# ME433.net
KiCad netlist of a schematic drawn in EAGLE
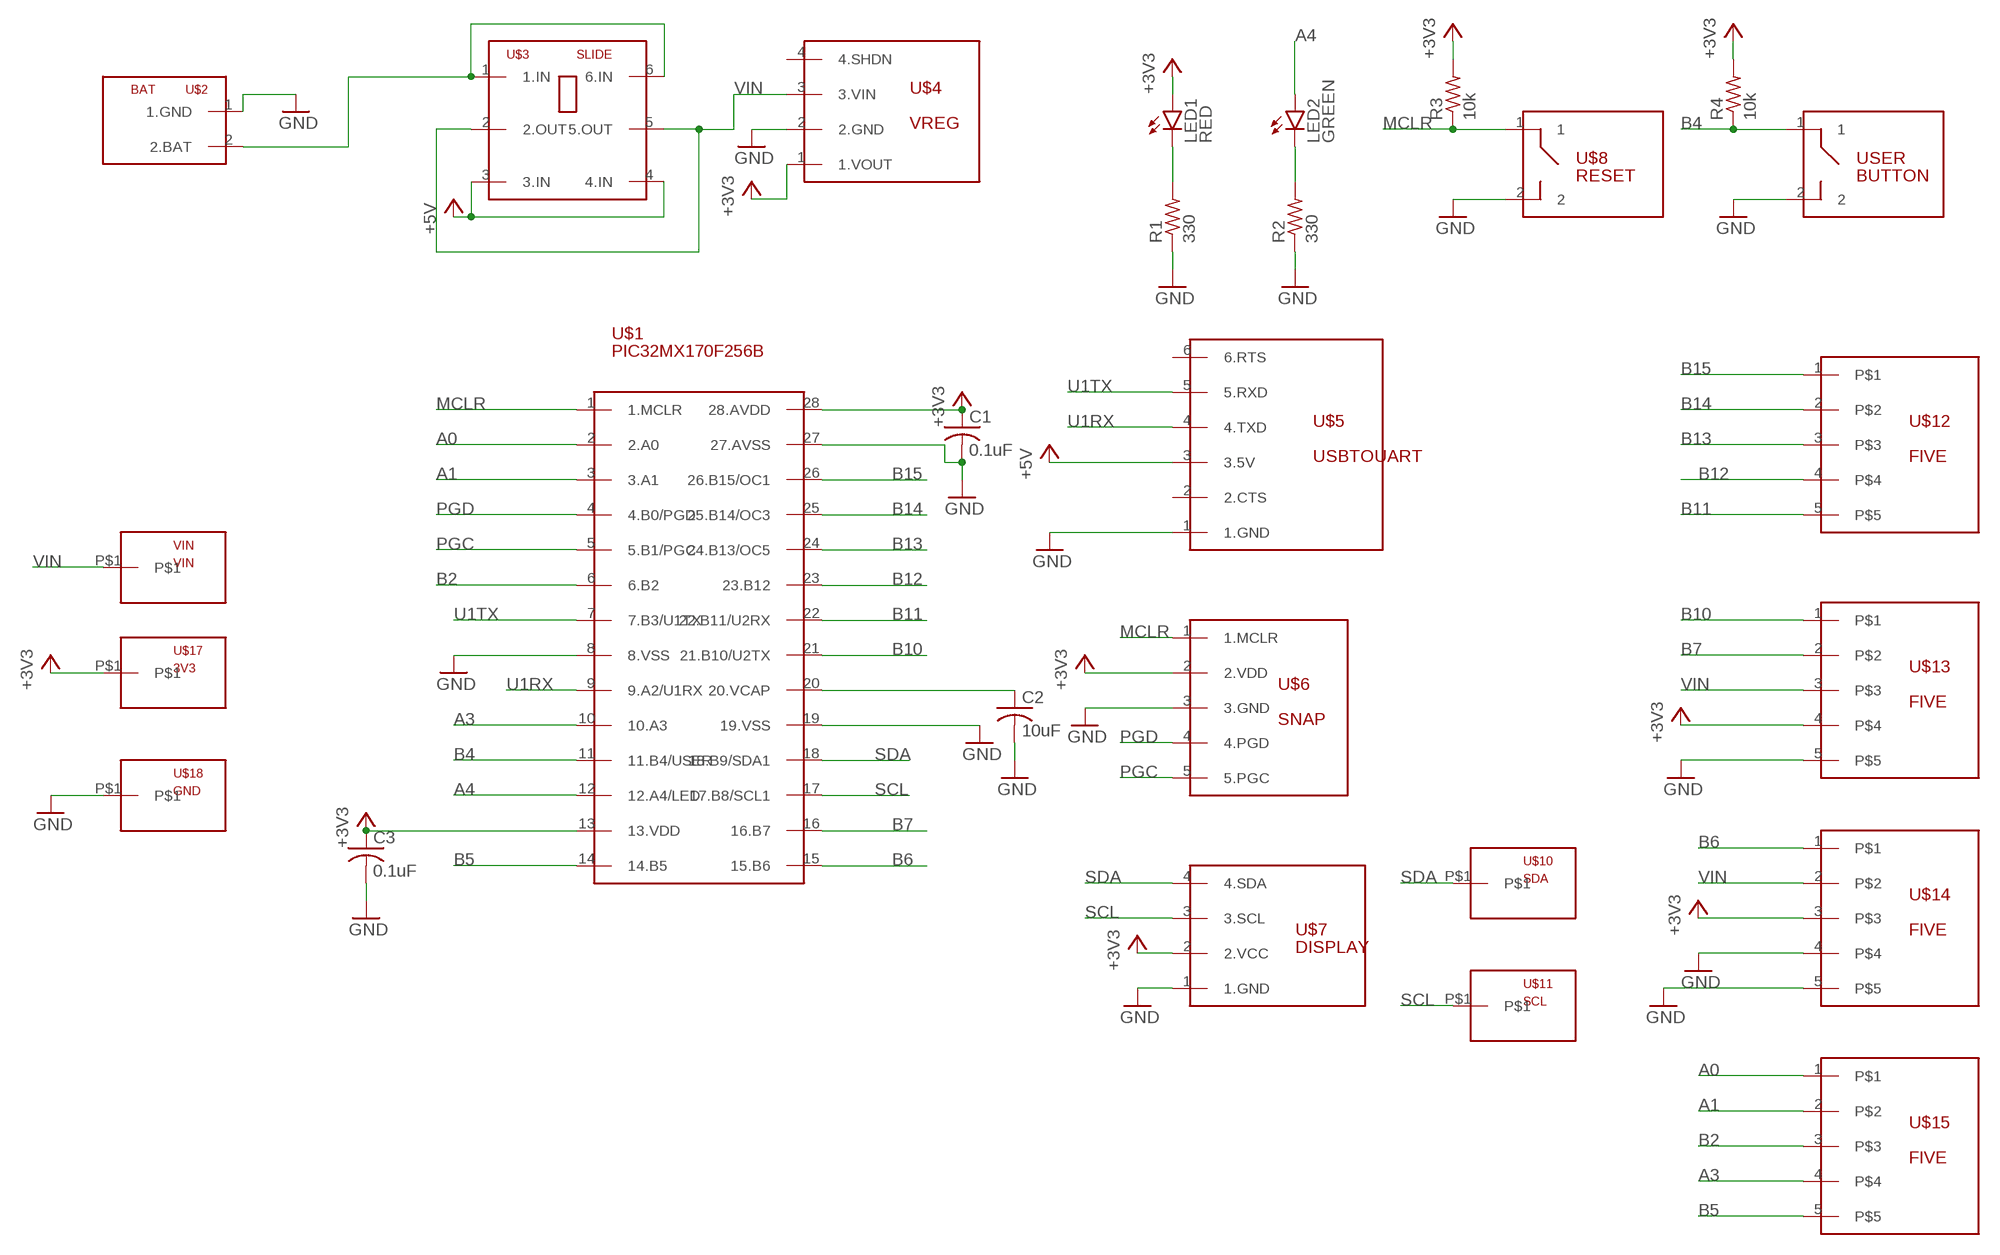
[diagram p0: schematic, sheet 1]

(export (version "E")
  (design (tool "Eeschema 10.0.6"))
  (components
    (comp (ref "C1")
      (value "0.1uF")
      (footprint "eagle-import:C025-024X044")
      (libsource (lib "eagle-import") (part "C-US025-024X044"))
    )
    (comp (ref "C2")
      (value "10uF")
      (footprint "eagle-import:C025-024X044")
      (libsource (lib "eagle-import") (part "C-US025-024X044"))
    )
    (comp (ref "C3")
      (value "0.1uF")
      (footprint "eagle-import:C025-024X044")
      (libsource (lib "eagle-import") (part "C-US025-024X044"))
    )
    (comp (ref "LED1")
      (value "RED")
      (footprint "eagle-import:LED3MM")
      (libsource (lib "eagle-import") (part "LED3MM"))
    )
    (comp (ref "LED2")
      (value "GREEN")
      (footprint "eagle-import:LED3MM")
      (libsource (lib "eagle-import") (part "LED3MM"))
    )
    (comp (ref "R1")
      (value "330")
      (footprint "eagle-import:0207_7")
      (libsource (lib "eagle-import") (part "R-US_0207/7"))
    )
    (comp (ref "R2")
      (value "330")
      (footprint "eagle-import:0207_7")
      (libsource (lib "eagle-import") (part "R-US_0207/7"))
    )
    (comp (ref "R3")
      (value "10k")
      (footprint "eagle-import:0207_7")
      (libsource (lib "eagle-import") (part "R-US_0207/7"))
    )
    (comp (ref "R4")
      (value "10k")
      (footprint "eagle-import:0207_7")
      (libsource (lib "eagle-import") (part "R-US_0207/7"))
    )
    (comp (ref "U$1")
      (value "PIC32MX170F256B")
      (footprint "eagle-import:DIL28-3")
      (libsource (lib "eagle-import") (part "PIC32MX170F256B"))
    )
    (comp (ref "U$2")
      (value "BAT")
      (footprint "eagle-import:BAT")
      (libsource (lib "eagle-import") (part "BAT"))
    )
    (comp (ref "U$3")
      (value "SLIDE")
      (footprint "eagle-import:SLIDE")
      (libsource (lib "eagle-import") (part "SLIDE"))
    )
    (comp (ref "U$4")
      (value "VREG")
      (footprint "eagle-import:VREG")
      (libsource (lib "eagle-import") (part "VREG"))
    )
    (comp (ref "U$5")
      (value "USBTOUART")
      (footprint "eagle-import:USBTOUART")
      (libsource (lib "eagle-import") (part "USBTOUART"))
    )
    (comp (ref "U$6")
      (value "SNAP")
      (footprint "eagle-import:SNAP")
      (libsource (lib "eagle-import") (part "SNAP"))
    )
    (comp (ref "U$7")
      (value "DISPLAY")
      (footprint "eagle-import:DISPLAY")
      (libsource (lib "eagle-import") (part "DISPLAY"))
    )
    (comp (ref "U$8")
      (value "RESET")
      (footprint "eagle-import:BUTTON")
      (libsource (lib "eagle-import") (part "BUTTON"))
    )
    (comp (ref "U$10") (value "SDA") (footprint "eagle-import:1") (libsource (lib "eagle-import") (part "1")))
    (comp (ref "U$11") (value "SCL") (footprint "eagle-import:1") (libsource (lib "eagle-import") (part "1")))
    (comp (ref "U$12")
      (value "FIVE")
      (footprint "eagle-import:FIVE")
      (libsource (lib "eagle-import") (part "FIVE"))
    )
    (comp (ref "U$13")
      (value "FIVE")
      (footprint "eagle-import:FIVE")
      (libsource (lib "eagle-import") (part "FIVE"))
    )
    (comp (ref "U$14")
      (value "FIVE")
      (footprint "eagle-import:FIVE")
      (libsource (lib "eagle-import") (part "FIVE"))
    )
    (comp (ref "U$15")
      (value "FIVE")
      (footprint "eagle-import:FIVE")
      (libsource (lib "eagle-import") (part "FIVE"))
    )
    (comp (ref "U$17") (value "3V3") (footprint "eagle-import:1") (libsource (lib "eagle-import") (part "1")))
    (comp (ref "U$18") (value "GND") (footprint "eagle-import:1") (libsource (lib "eagle-import") (part "1")))
    (comp (ref "USER")
      (value "BUTTON")
      (footprint "eagle-import:BUTTON")
      (libsource (lib "eagle-import") (part "BUTTON"))
    )
    (comp (ref "VIN") (value "VIN") (footprint "eagle-import:1") (libsource (lib "eagle-import") (part "1")))
  )
  (nets
    (net (code "1") (name "+3V3") (class "Default")
      (node (ref "C1") (pin "1") (pinfunction "1_1") (pintype "passive"))
      (node (ref "C3") (pin "1") (pinfunction "1_1") (pintype "passive"))
      (node (ref "LED1") (pin "A") (pinfunction "A_A") (pintype "passive"))
      (node (ref "R3") (pin "2") (pinfunction "2_2") (pintype "passive"))
      (node (ref "R4") (pin "2") (pinfunction "2_2") (pintype "passive"))
      (node (ref "U$1") (pin "13") (pinfunction "13.VDD_13") (pintype "bidirectional"))
      (node (ref "U$1") (pin "28") (pinfunction "28.AVDD_28") (pintype "bidirectional"))
      (node (ref "U$13") (pin "4") (pinfunction "P$4_4") (pintype "bidirectional"))
      (node (ref "U$14") (pin "3") (pinfunction "P$3_3") (pintype "bidirectional"))
      (node (ref "U$17") (pin "P$1") (pinfunction "P$1_P$1") (pintype "bidirectional"))
      (node (ref "U$4") (pin "1") (pinfunction "1.VOUT_1") (pintype "bidirectional"))
      (node (ref "U$6") (pin "2") (pinfunction "2.VDD_2") (pintype "bidirectional"))
      (node (ref "U$7") (pin "2") (pinfunction "2.VCC_2") (pintype "bidirectional"))
    )
    (net (code "2") (name "+5V") (class "Default")
      (node (ref "U$3") (pin "3") (pinfunction "3.IN_3") (pintype "bidirectional"))
      (node (ref "U$3") (pin "4") (pinfunction "4.IN_4") (pintype "bidirectional"))
      (node (ref "U$5") (pin "3") (pinfunction "3.5V_3") (pintype "bidirectional"))
    )
    (net (code "3") (name "/A0") (class "Default")
      (node (ref "U$1") (pin "2") (pinfunction "2.A0_2") (pintype "bidirectional"))
      (node (ref "U$15") (pin "1") (pinfunction "P$1_1") (pintype "bidirectional"))
    )
    (net (code "4") (name "/A1") (class "Default")
      (node (ref "U$1") (pin "3") (pinfunction "3.A1_3") (pintype "bidirectional"))
      (node (ref "U$15") (pin "2") (pinfunction "P$2_2") (pintype "bidirectional"))
    )
    (net (code "5") (name "/A3") (class "Default")
      (node (ref "U$1") (pin "10") (pinfunction "10.A3_10") (pintype "bidirectional"))
      (node (ref "U$15") (pin "4") (pinfunction "P$4_4") (pintype "bidirectional"))
    )
    (net (code "6") (name "/A4") (class "Default")
      (node (ref "LED2") (pin "A") (pinfunction "A_A") (pintype "passive"))
      (node (ref "U$1") (pin "12") (pinfunction "12.A4/LED_12") (pintype "bidirectional"))
    )
    (net (code "7") (name "/B2") (class "Default")
      (node (ref "U$1") (pin "6") (pinfunction "6.B2_6") (pintype "bidirectional"))
      (node (ref "U$15") (pin "3") (pinfunction "P$3_3") (pintype "bidirectional"))
    )
    (net (code "8") (name "/B4") (class "Default")
      (node (ref "R4") (pin "1") (pinfunction "1_1") (pintype "passive"))
      (node (ref "U$1") (pin "11") (pinfunction "11.B4/USER_11") (pintype "bidirectional"))
      (node (ref "USER") (pin "1") (pinfunction "1_1") (pintype "bidirectional"))
    )
    (net (code "9") (name "/B5") (class "Default")
      (node (ref "U$1") (pin "14") (pinfunction "14.B5_14") (pintype "bidirectional"))
      (node (ref "U$15") (pin "5") (pinfunction "P$5_5") (pintype "bidirectional"))
    )
    (net (code "10") (name "/B6") (class "Default")
      (node (ref "U$1") (pin "15") (pinfunction "15.B6_15") (pintype "bidirectional"))
      (node (ref "U$14") (pin "1") (pinfunction "P$1_1") (pintype "bidirectional"))
    )
    (net (code "11") (name "/B7") (class "Default")
      (node (ref "U$1") (pin "16") (pinfunction "16.B7_16") (pintype "bidirectional"))
      (node (ref "U$13") (pin "2") (pinfunction "P$2_2") (pintype "bidirectional"))
    )
    (net (code "12") (name "/B10") (class "Default")
      (node (ref "U$1") (pin "21") (pinfunction "21.B10/U2TX_21") (pintype "bidirectional"))
      (node (ref "U$13") (pin "1") (pinfunction "P$1_1") (pintype "bidirectional"))
    )
    (net (code "13") (name "/B11") (class "Default")
      (node (ref "U$1") (pin "22") (pinfunction "22.B11/U2RX_22") (pintype "bidirectional"))
      (node (ref "U$12") (pin "5") (pinfunction "P$5_5") (pintype "bidirectional"))
    )
    (net (code "14") (name "/B12") (class "Default")
      (node (ref "U$1") (pin "23") (pinfunction "23.B12_23") (pintype "bidirectional"))
      (node (ref "U$12") (pin "4") (pinfunction "P$4_4") (pintype "bidirectional"))
    )
    (net (code "15") (name "/B13") (class "Default")
      (node (ref "U$1") (pin "24") (pinfunction "24.B13/OC5_24") (pintype "bidirectional"))
      (node (ref "U$12") (pin "3") (pinfunction "P$3_3") (pintype "bidirectional"))
    )
    (net (code "16") (name "/B14") (class "Default")
      (node (ref "U$1") (pin "25") (pinfunction "25.B14/OC3_25") (pintype "bidirectional"))
      (node (ref "U$12") (pin "2") (pinfunction "P$2_2") (pintype "bidirectional"))
    )
    (net (code "17") (name "/B15") (class "Default")
      (node (ref "U$1") (pin "26") (pinfunction "26.B15/OC1_26") (pintype "bidirectional"))
      (node (ref "U$12") (pin "1") (pinfunction "P$1_1") (pintype "bidirectional"))
    )
    (net (code "18") (name "/MCLR") (class "Default")
      (node (ref "R3") (pin "1") (pinfunction "1_1") (pintype "passive"))
      (node (ref "U$1") (pin "1") (pinfunction "1.MCLR_1") (pintype "bidirectional"))
      (node (ref "U$6") (pin "1") (pinfunction "1.MCLR_1") (pintype "bidirectional"))
      (node (ref "U$8") (pin "1") (pinfunction "1_1") (pintype "bidirectional"))
    )
    (net (code "19") (name "/PGC") (class "Default")
      (node (ref "U$1") (pin "5") (pinfunction "5.B1/PGC_5") (pintype "bidirectional"))
      (node (ref "U$6") (pin "5") (pinfunction "5.PGC_5") (pintype "bidirectional"))
    )
    (net (code "20") (name "/PGD") (class "Default")
      (node (ref "U$1") (pin "4") (pinfunction "4.B0/PGD_4") (pintype "bidirectional"))
      (node (ref "U$6") (pin "4") (pinfunction "4.PGD_4") (pintype "bidirectional"))
    )
    (net (code "21") (name "/SCL") (class "Default")
      (node (ref "U$1") (pin "17") (pinfunction "17.B8/SCL1_17") (pintype "bidirectional"))
      (node (ref "U$11") (pin "P$1") (pinfunction "P$1_P$1") (pintype "bidirectional"))
      (node (ref "U$7") (pin "3") (pinfunction "3.SCL_3") (pintype "bidirectional"))
    )
    (net (code "22") (name "/SDA") (class "Default")
      (node (ref "U$1") (pin "18") (pinfunction "18.B9/SDA1_18") (pintype "bidirectional"))
      (node (ref "U$10") (pin "P$1") (pinfunction "P$1_P$1") (pintype "bidirectional"))
      (node (ref "U$7") (pin "4") (pinfunction "4.SDA_4") (pintype "bidirectional"))
    )
    (net (code "23") (name "/U1RX") (class "Default")
      (node (ref "U$1") (pin "9") (pinfunction "9.A2/U1RX_9") (pintype "bidirectional"))
      (node (ref "U$5") (pin "4") (pinfunction "4.TXD_4") (pintype "bidirectional"))
    )
    (net (code "24") (name "/U1TX") (class "Default")
      (node (ref "U$1") (pin "7") (pinfunction "7.B3/U1TX_7") (pintype "bidirectional"))
      (node (ref "U$5") (pin "5") (pinfunction "5.RXD_5") (pintype "bidirectional"))
    )
    (net (code "25") (name "/VIN") (class "Default")
      (node (ref "U$13") (pin "3") (pinfunction "P$3_3") (pintype "bidirectional"))
      (node (ref "U$14") (pin "2") (pinfunction "P$2_2") (pintype "bidirectional"))
      (node (ref "U$3") (pin "2") (pinfunction "2.OUT_2") (pintype "bidirectional"))
      (node (ref "U$3") (pin "5") (pinfunction "5.OUT_5") (pintype "bidirectional"))
      (node (ref "U$4") (pin "3") (pinfunction "3.VIN_3") (pintype "bidirectional"))
      (node (ref "VIN") (pin "P$1") (pinfunction "P$1_P$1") (pintype "bidirectional"))
    )
    (net (code "26") (name "GND") (class "Default")
      (node (ref "C1") (pin "2") (pinfunction "2_2") (pintype "passive"))
      (node (ref "C2") (pin "2") (pinfunction "2_2") (pintype "passive"))
      (node (ref "C3") (pin "2") (pinfunction "2_2") (pintype "passive"))
      (node (ref "R1") (pin "1") (pinfunction "1_1") (pintype "passive"))
      (node (ref "R2") (pin "1") (pinfunction "1_1") (pintype "passive"))
      (node (ref "U$1") (pin "19") (pinfunction "19.VSS_19") (pintype "bidirectional"))
      (node (ref "U$1") (pin "27") (pinfunction "27.AVSS_27") (pintype "bidirectional"))
      (node (ref "U$1") (pin "8") (pinfunction "8.VSS_8") (pintype "bidirectional"))
      (node (ref "U$13") (pin "5") (pinfunction "P$5_5") (pintype "bidirectional"))
      (node (ref "U$14") (pin "4") (pinfunction "P$4_4") (pintype "bidirectional"))
      (node (ref "U$14") (pin "5") (pinfunction "P$5_5") (pintype "bidirectional"))
      (node (ref "U$18") (pin "P$1") (pinfunction "P$1_P$1") (pintype "bidirectional"))
      (node (ref "U$2") (pin "1") (pinfunction "1.GND_1") (pintype "bidirectional"))
      (node (ref "U$4") (pin "2") (pinfunction "2.GND_2") (pintype "bidirectional"))
      (node (ref "U$5") (pin "1") (pinfunction "1.GND_1") (pintype "bidirectional"))
      (node (ref "U$6") (pin "3") (pinfunction "3.GND_3") (pintype "bidirectional"))
      (node (ref "U$7") (pin "1") (pinfunction "1.GND_1") (pintype "bidirectional"))
      (node (ref "U$8") (pin "2") (pinfunction "2_2") (pintype "bidirectional"))
      (node (ref "USER") (pin "2") (pinfunction "2_2") (pintype "bidirectional"))
    )
    (net (code "27") (name "Net-(LED1-C)") (class "Default")
      (node (ref "LED1") (pin "K") (pinfunction "C_K") (pintype "passive"))
      (node (ref "R1") (pin "2") (pinfunction "2_2") (pintype "passive"))
    )
    (net (code "28") (name "Net-(LED2-C)") (class "Default")
      (node (ref "LED2") (pin "K") (pinfunction "C_K") (pintype "passive"))
      (node (ref "R2") (pin "2") (pinfunction "2_2") (pintype "passive"))
    )
    (net (code "29") (name "Net-(U$1-20.VCAP)") (class "Default")
      (node (ref "C2") (pin "1") (pinfunction "1_1") (pintype "passive"))
      (node (ref "U$1") (pin "20") (pinfunction "20.VCAP_20") (pintype "bidirectional"))
    )
    (net (code "30") (name "Net-(U$2-2.BAT)") (class "Default")
      (node (ref "U$2") (pin "2") (pinfunction "2.BAT_2") (pintype "bidirectional"))
      (node (ref "U$3") (pin "1") (pinfunction "1.IN_1") (pintype "bidirectional"))
      (node (ref "U$3") (pin "6") (pinfunction "6.IN_6") (pintype "bidirectional"))
    )
    (net (code "31") (name "unconnected-(U$4-4.SHDN-Pad4)") (class "Default")
      (node (ref "U$4") (pin "4") (pinfunction "4.SHDN_4") (pintype "bidirectional"))
    )
    (net (code "32") (name "unconnected-(U$5-2.CTS-Pad2)") (class "Default")
      (node (ref "U$5") (pin "2") (pinfunction "2.CTS_2") (pintype "bidirectional"))
    )
    (net (code "33") (name "unconnected-(U$5-6.RTS-Pad6)") (class "Default")
      (node (ref "U$5") (pin "6") (pinfunction "6.RTS_6") (pintype "bidirectional"))
    )
  )
)
